# Fri3D_IRA_00.net
KiCad netlist of a schematic drawn in Altium Designer
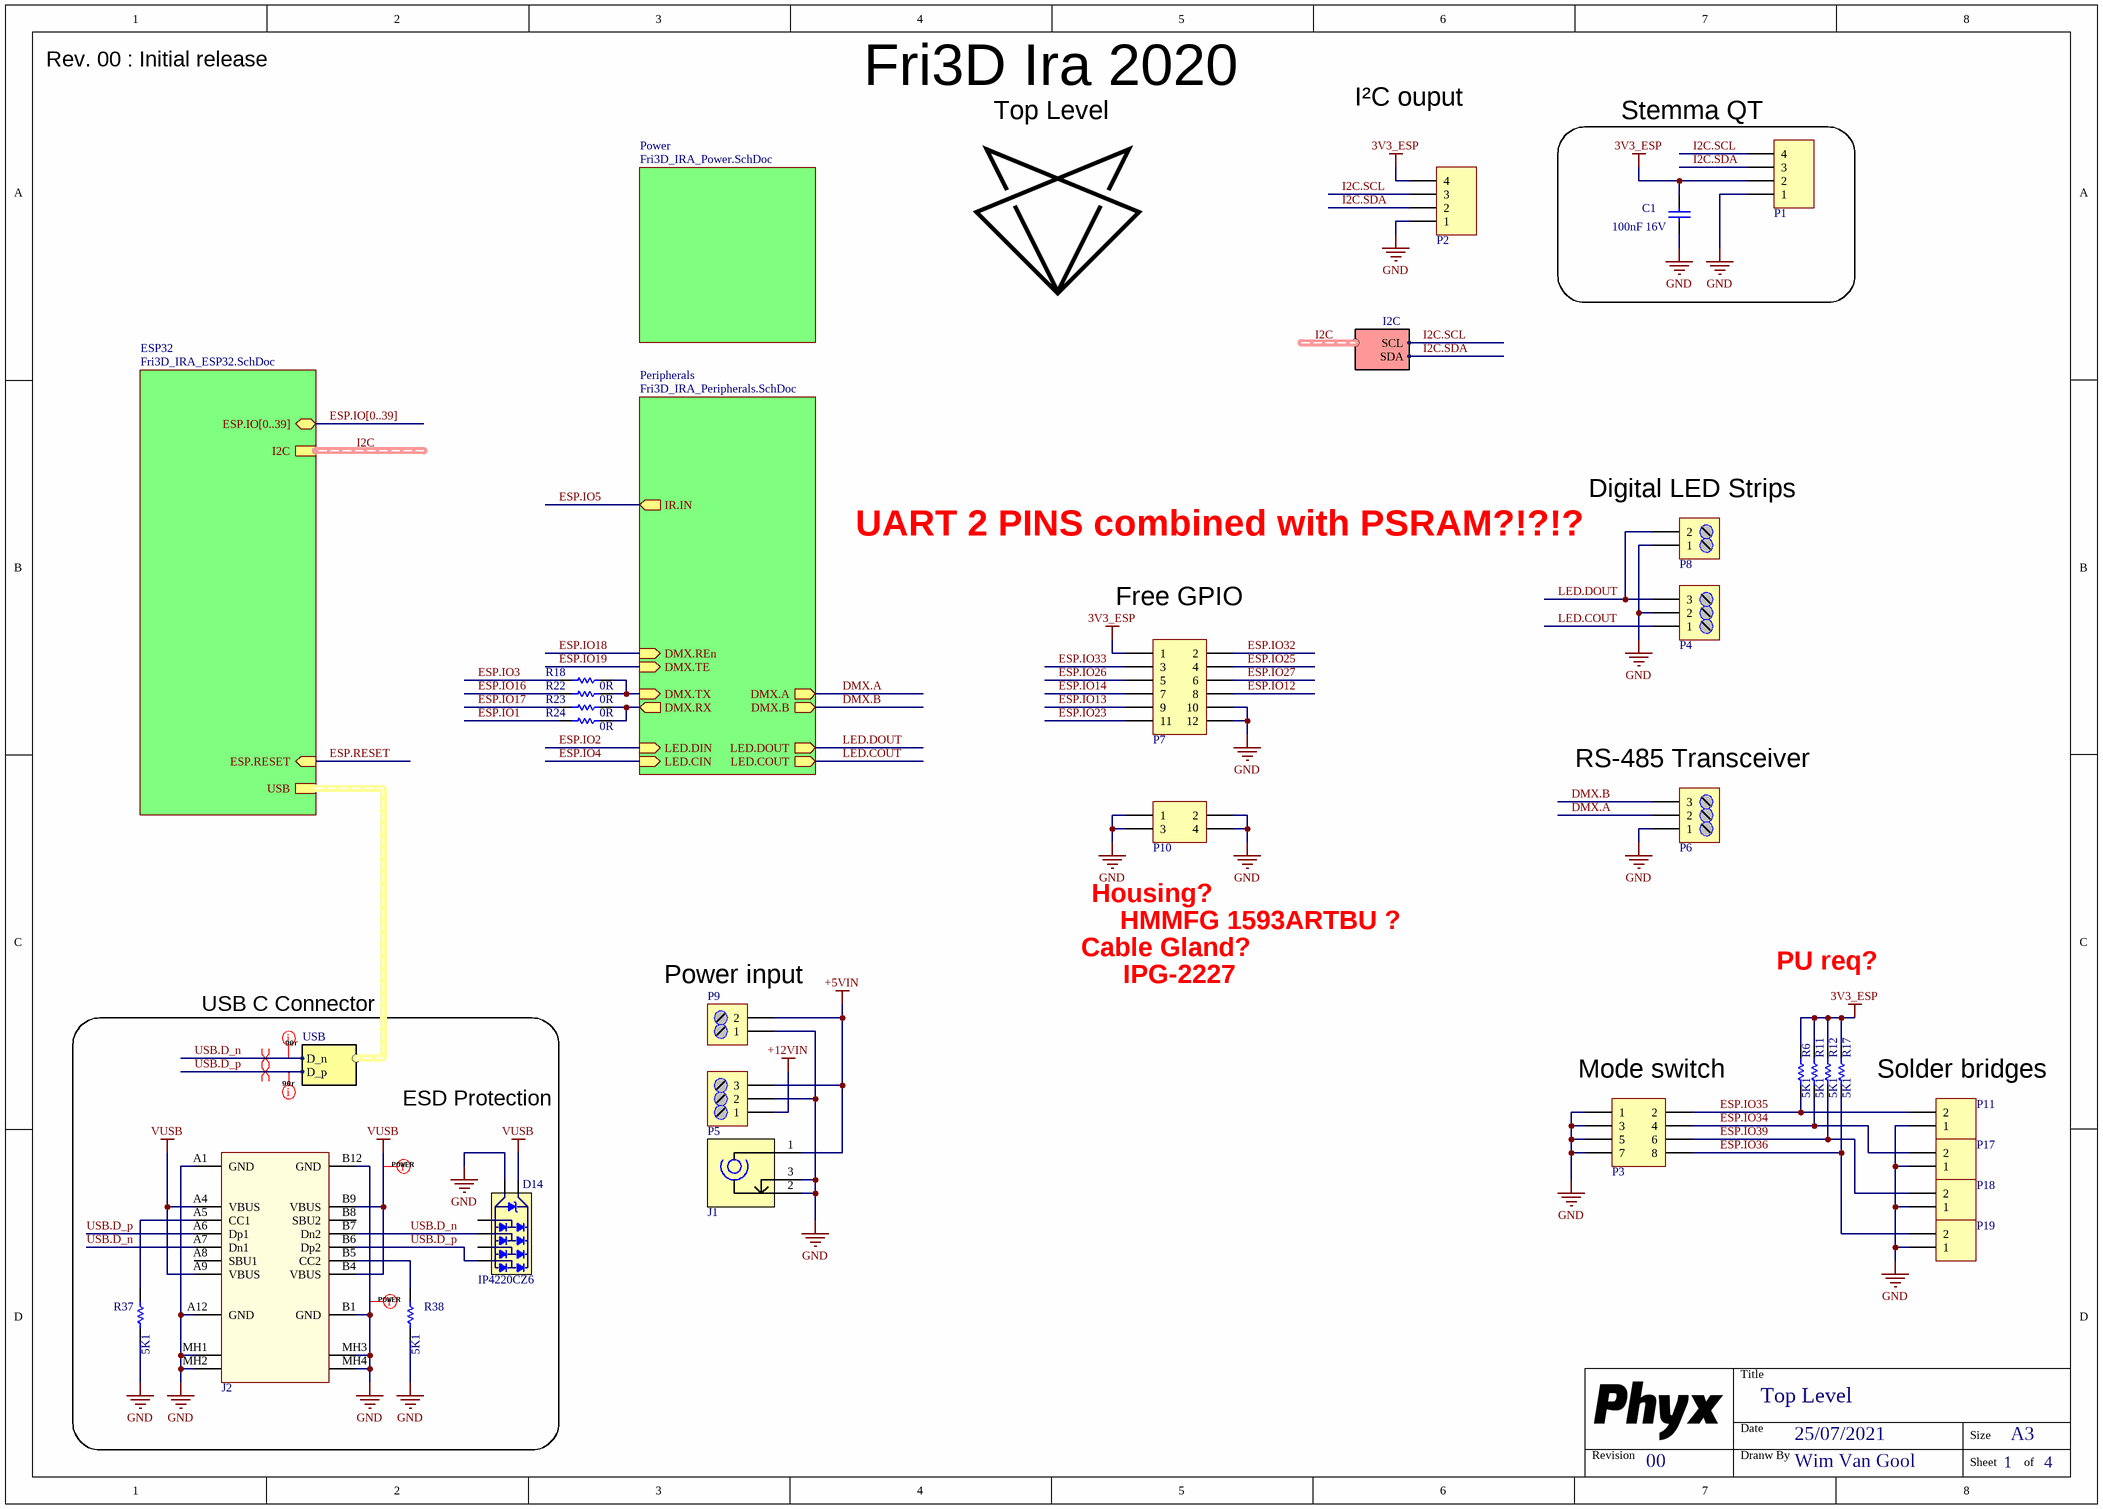
[diagram p0: Fri3D_IRA_00.SchDoc]

(export (version "E")
  (design (tool "Eeschema 10.0.6"))
  (components
    (comp (ref "C1")
      (value "100nF 16V")
      (footprint "C0603_N")
      (description "Capacitor Ceramic")
      (libsource (lib "Phyx_Components") (part "CAP_CERAMIC"))
    )
    (comp (ref "D14")
      (value "IP4220CZ6")
      (footprint "NXP_SOT457")
      (description "=Description")
      (fields (field (name "Comment") "TVS Diode Dual USB"))
      (libsource (lib "Phyx_Components") (part "NXP_IP4220CZ6"))
    )
    (comp (ref "J1")
      (value "Socket RA 5.5  with 2.5 barrel")
      (footprint "Cliff_DC10")
      (description "=Description")
      (libsource (lib "Phyx_Components") (part "Cliff_DC10"))
    )
    (comp (ref "J2")
      (value "USB 2.0 C Reversible Receptacle Horizontal")
      (footprint "HRO_TYPE-C-31-M-12")
      (libsource (lib "Phyx_Components") (part "USB_C_16_4"))
    )
    (comp (ref "P1")
      (value "Header 1.0mm RA Shrouded 4")
      (footprint "WE_665104131822")
      (libsource (lib "Phyx_Components") (part "Header 4"))
    )
    (comp (ref "P2")
      (value "Header 4")
      (footprint "HDR1X4")
      (libsource (lib "Phyx_Components") (part "Header 4"))
    )
    (comp (ref "P3")
      (value "Header 4x2")
      (footprint "HDR2X4")
      (libsource (lib "Phyx_Components") (part "Header 4X2"))
    )
    (comp (ref "P4")
      (value "3 Way Screw HDR 5,08mm")
      (footprint "TERM_BLK-0508-3-90")
      (libsource (lib "") (part "TERM_BLCK_3_1"))
    )
    (comp (ref "P5")
      (value "3 Way Screw HDR 5,08mm")
      (footprint "TERM_BLK-0508-3-90")
      (libsource (lib "Phyx_Components") (part "TERM_BLCK_3"))
    )
    (comp (ref "P6")
      (value "3 Way Screw HDR 5,08mm")
      (footprint "TERM_BLK-0508-3-90")
      (libsource (lib "") (part "TERM_BLCK_3_1"))
    )
    (comp (ref "P7")
      (value "Header 6X2")
      (footprint "HDR2X6")
      (libsource (lib "Phyx_Components") (part "Header 6X2"))
    )
    (comp (ref "P8")
      (value "2 Way Screw HDR 5,08mm")
      (footprint "TERM_BLK-0508-2-90")
      (libsource (lib "") (part "TERM_BLCK_2_1"))
    )
    (comp (ref "P9")
      (value "2 Way Screw HDR 5,08mm")
      (footprint "TERM_BLK-0508-2-90")
      (libsource (lib "Phyx_Components") (part "TERM_BLCK_2"))
    )
    (comp (ref "P10")
      (value "Header 2X2")
      (footprint "HDR2X2")
      (libsource (lib "Phyx_Components") (part "Header 2X2"))
    )
    (comp (ref "P11")
      (value "Easy to solder connection")
      (footprint "SOLDER_SW_V_1MM")
      (libsource (lib "Phyx_Components") (part "Header 2"))
    )
    (comp (ref "P17")
      (value "Easy to solder connection")
      (footprint "SOLDER_SW_V_1MM")
      (libsource (lib "Phyx_Components") (part "Header 2"))
    )
    (comp (ref "P18")
      (value "Easy to solder connection")
      (footprint "SOLDER_SW_V_1MM")
      (libsource (lib "Phyx_Components") (part "Header 2"))
    )
    (comp (ref "P19")
      (value "Easy to solder connection")
      (footprint "SOLDER_SW_V_1MM")
      (libsource (lib "Phyx_Components") (part "Header 2"))
    )
    (comp (ref "R6")
      (value "5K1")
      (footprint "R0603_N")
      (fields (field (name "Comment") "RESISTOR"))
      (libsource (lib "Phyx_Components") (part "RESISTOR"))
    )
    (comp (ref "R11")
      (value "5K1")
      (footprint "R0603_N")
      (fields (field (name "Comment") "RESISTOR"))
      (libsource (lib "Phyx_Components") (part "RESISTOR"))
    )
    (comp (ref "R12")
      (value "5K1")
      (footprint "R0603_N")
      (fields (field (name "Comment") "RESISTOR"))
      (libsource (lib "Phyx_Components") (part "RESISTOR"))
    )
    (comp (ref "R17")
      (value "5K1")
      (footprint "R0603_N")
      (fields (field (name "Comment") "RESISTOR"))
      (libsource (lib "Phyx_Components") (part "RESISTOR"))
    )
    (comp (ref "R18")
      (value "0R")
      (footprint "R0603_N")
      (description "RES # 0R 0603")
      (fields (field (name "Comment") "RESISTOR"))
      (libsource (lib "Phyx_Components") (part "RESISTOR"))
    )
    (comp (ref "R22")
      (value "0R")
      (footprint "R0603_N")
      (description "RES # 0R 0603")
      (fields (field (name "Comment") "RESISTOR"))
      (libsource (lib "Phyx_Components") (part "RESISTOR"))
    )
    (comp (ref "R23")
      (value "0R")
      (footprint "R0603_N")
      (description "RES # 0R 0603")
      (fields (field (name "Comment") "RESISTOR"))
      (libsource (lib "Phyx_Components") (part "RESISTOR"))
    )
    (comp (ref "R24")
      (value "0R")
      (footprint "R0603_N")
      (description "RES # 0R 0603")
      (fields (field (name "Comment") "RESISTOR"))
      (libsource (lib "Phyx_Components") (part "RESISTOR"))
    )
    (comp (ref "R37")
      (value "5K1")
      (footprint "R0603_N")
      (fields (field (name "Comment") "RESISTOR"))
      (libsource (lib "Phyx_Components") (part "RESISTOR"))
    )
    (comp (ref "R38")
      (value "5K1")
      (footprint "R0603_N")
      (fields (field (name "Comment") "RESISTOR"))
      (libsource (lib "Phyx_Components") (part "RESISTOR"))
    )
  )
  (nets
    (net (code "22") (name "+5VIN") (class "Default")
      (node (ref "J1") (pin "1") (pinfunction "1_1") (pintype "passive"))
      (node (ref "P5") (pin "3") (pinfunction "3_3") (pintype "passive"))
      (node (ref "P9") (pin "2") (pinfunction "2_2") (pintype "passive"))
    )
    (net (code "23") (name "+12VIN") (class "Default")
      (node (ref "P5") (pin "1") (pinfunction "1_1") (pintype "passive"))
    )
    (net (code "25") (name "/DMX.A") (class "Default")
      (node (ref "P6") (pin "2") (pinfunction "2_2") (pintype "passive"))
    )
    (net (code "26") (name "/DMX.B") (class "Default")
      (node (ref "P6") (pin "3") (pinfunction "3_3") (pintype "passive"))
    )
    (net (code "27") (name "/DMX.RX") (class "Default")
      (node (ref "R23") (pin "1") (pinfunction "1_1") (pintype "passive"))
      (node (ref "R24") (pin "1") (pinfunction "1_1") (pintype "passive"))
    )
    (net (code "28") (name "/DMX.TX") (class "Default")
      (node (ref "R18") (pin "1") (pinfunction "1_1") (pintype "passive"))
      (node (ref "R22") (pin "1") (pinfunction "1_1") (pintype "passive"))
    )
    (net (code "29") (name "/ESP.IO1") (class "Default")
      (node (ref "R24") (pin "2") (pinfunction "2_2") (pintype "passive"))
    )
    (net (code "31") (name "/ESP.IO3") (class "Default")
      (node (ref "R18") (pin "2") (pinfunction "2_2") (pintype "passive"))
    )
    (net (code "34") (name "/ESP.IO12") (class "Default")
      (node (ref "P7") (pin "8") (pinfunction "8_8") (pintype "passive"))
    )
    (net (code "35") (name "/ESP.IO13") (class "Default")
      (node (ref "P7") (pin "9") (pinfunction "9_9") (pintype "passive"))
    )
    (net (code "36") (name "/ESP.IO14") (class "Default")
      (node (ref "P7") (pin "7") (pinfunction "7_7") (pintype "passive"))
    )
    (net (code "37") (name "/ESP.IO16") (class "Default")
      (node (ref "R22") (pin "2") (pinfunction "2_2") (pintype "passive"))
    )
    (net (code "38") (name "/ESP.IO17") (class "Default")
      (node (ref "R23") (pin "2") (pinfunction "2_2") (pintype "passive"))
    )
    (net (code "41") (name "/ESP.IO23") (class "Default")
      (node (ref "P7") (pin "11") (pinfunction "11_11") (pintype "passive"))
    )
    (net (code "42") (name "/ESP.IO25") (class "Default")
      (node (ref "P7") (pin "4") (pinfunction "4_4") (pintype "passive"))
    )
    (net (code "43") (name "/ESP.IO26") (class "Default")
      (node (ref "P7") (pin "5") (pinfunction "5_5") (pintype "passive"))
    )
    (net (code "44") (name "/ESP.IO27") (class "Default")
      (node (ref "P7") (pin "6") (pinfunction "6_6") (pintype "passive"))
    )
    (net (code "45") (name "/ESP.IO32") (class "Default")
      (node (ref "P7") (pin "2") (pinfunction "2_2") (pintype "passive"))
    )
    (net (code "46") (name "/ESP.IO33") (class "Default")
      (node (ref "P7") (pin "3") (pinfunction "3_3") (pintype "passive"))
    )
    (net (code "47") (name "/ESP.IO34") (class "Default")
      (node (ref "P17") (pin "2") (pinfunction "2_2") (pintype "passive"))
      (node (ref "P3") (pin "4") (pinfunction "4_4") (pintype "passive"))
      (node (ref "R11") (pin "2") (pinfunction "2_2") (pintype "passive"))
    )
    (net (code "48") (name "/ESP.IO35") (class "Default")
      (node (ref "P11") (pin "2") (pinfunction "2_2") (pintype "passive"))
      (node (ref "P3") (pin "2") (pinfunction "2_2") (pintype "passive"))
      (node (ref "R6") (pin "2") (pinfunction "2_2") (pintype "passive"))
    )
    (net (code "49") (name "/ESP.IO36") (class "Default")
      (node (ref "P19") (pin "2") (pinfunction "2_2") (pintype "passive"))
      (node (ref "P3") (pin "8") (pinfunction "8_8") (pintype "passive"))
      (node (ref "R17") (pin "2") (pinfunction "2_2") (pintype "passive"))
    )
    (net (code "50") (name "/ESP.IO39") (class "Default")
      (node (ref "P18") (pin "2") (pinfunction "2_2") (pintype "passive"))
      (node (ref "P3") (pin "6") (pinfunction "6_6") (pintype "passive"))
      (node (ref "R12") (pin "2") (pinfunction "2_2") (pintype "passive"))
    )
    (net (code "53") (name "/I2C.SCL") (class "Default")
      (node (ref "P1") (pin "4") (pinfunction "4_4") (pintype "passive"))
      (node (ref "P2") (pin "3") (pinfunction "3_3") (pintype "passive"))
    )
    (net (code "54") (name "/I2C.SDA") (class "Default")
      (node (ref "P1") (pin "3") (pinfunction "3_3") (pintype "passive"))
      (node (ref "P2") (pin "2") (pinfunction "2_2") (pintype "passive"))
    )
    (net (code "56") (name "/LED.COUT") (class "Default")
      (node (ref "P4") (pin "1") (pinfunction "1_1") (pintype "passive"))
    )
    (net (code "57") (name "/LED.DOUT") (class "Default")
      (node (ref "P4") (pin "3") (pinfunction "3_3") (pintype "passive"))
      (node (ref "P8") (pin "2") (pinfunction "2_2") (pintype "passive"))
    )
    (net (code "58") (name "/USB.D_n") (class "Default")
      (node (ref "D14") (pin "1") (pinfunction "1_1") (pintype "passive"))
      (node (ref "J2") (pin "A7") (pinfunction "Dn1_A7") (pintype "passive"))
      (node (ref "J2") (pin "B7") (pinfunction "Dn2_B7") (pintype "passive"))
    )
    (net (code "59") (name "/USB.D_p") (class "Default")
      (node (ref "D14") (pin "6") (pinfunction "6_6") (pintype "passive"))
      (node (ref "J2") (pin "A6") (pinfunction "Dp1_A6") (pintype "passive"))
      (node (ref "J2") (pin "B6") (pinfunction "Dp2_B6") (pintype "passive"))
    )
    (net (code "62") (name "3V3_ESP") (class "Default")
      (node (ref "C1") (pin "1") (pinfunction "1_1") (pintype "passive"))
      (node (ref "P1") (pin "2") (pinfunction "2_2") (pintype "passive"))
      (node (ref "P2") (pin "4") (pinfunction "4_4") (pintype "passive"))
      (node (ref "P7") (pin "1") (pinfunction "1_1") (pintype "passive"))
      (node (ref "R11") (pin "1") (pinfunction "1_1") (pintype "passive"))
      (node (ref "R12") (pin "1") (pinfunction "1_1") (pintype "passive"))
      (node (ref "R17") (pin "1") (pinfunction "1_1") (pintype "passive"))
      (node (ref "R6") (pin "1") (pinfunction "1_1") (pintype "passive"))
    )
    (net (code "63") (name "GND") (class "Default")
      (node (ref "C1") (pin "2") (pinfunction "2_2") (pintype "passive"))
      (node (ref "D14") (pin "2") (pinfunction "GND_2") (pintype "passive"))
      (node (ref "J1") (pin "2") (pinfunction "2_2") (pintype "passive"))
      (node (ref "J1") (pin "3") (pinfunction "3_3") (pintype "passive"))
      (node (ref "J2") (pin "A1") (pinfunction "GND_A1") (pintype "passive"))
      (node (ref "J2") (pin "A12") (pinfunction "GND_A12") (pintype "passive"))
      (node (ref "J2") (pin "B1") (pinfunction "GND_B1") (pintype "passive"))
      (node (ref "J2") (pin "B12") (pinfunction "GND_B12") (pintype "passive"))
      (node (ref "J2") (pin "MH1") (pinfunction "Tab_MH1") (pintype "passive"))
      (node (ref "J2") (pin "MH2") (pinfunction "Tab_MH2") (pintype "passive"))
      (node (ref "J2") (pin "MH3") (pinfunction "Tab_MH3") (pintype "passive"))
      (node (ref "J2") (pin "MH4") (pinfunction "Tab_MH4") (pintype "passive"))
      (node (ref "P1") (pin "1") (pinfunction "1_1") (pintype "passive"))
      (node (ref "P10") (pin "1") (pinfunction "1_1") (pintype "passive"))
      (node (ref "P10") (pin "2") (pinfunction "2_2") (pintype "passive"))
      (node (ref "P10") (pin "3") (pinfunction "3_3") (pintype "passive"))
      (node (ref "P10") (pin "4") (pinfunction "4_4") (pintype "passive"))
      (node (ref "P11") (pin "1") (pinfunction "1_1") (pintype "passive"))
      (node (ref "P17") (pin "1") (pinfunction "1_1") (pintype "passive"))
      (node (ref "P18") (pin "1") (pinfunction "1_1") (pintype "passive"))
      (node (ref "P19") (pin "1") (pinfunction "1_1") (pintype "passive"))
      (node (ref "P2") (pin "1") (pinfunction "1_1") (pintype "passive"))
      (node (ref "P3") (pin "1") (pinfunction "1_1") (pintype "passive"))
      (node (ref "P3") (pin "3") (pinfunction "3_3") (pintype "passive"))
      (node (ref "P3") (pin "5") (pinfunction "5_5") (pintype "passive"))
      (node (ref "P3") (pin "7") (pinfunction "7_7") (pintype "passive"))
      (node (ref "P4") (pin "2") (pinfunction "2_2") (pintype "passive"))
      (node (ref "P5") (pin "2") (pinfunction "2_2") (pintype "passive"))
      (node (ref "P6") (pin "1") (pinfunction "1_1") (pintype "passive"))
      (node (ref "P7") (pin "10") (pinfunction "10_10") (pintype "passive"))
      (node (ref "P7") (pin "12") (pinfunction "12_12") (pintype "passive"))
      (node (ref "P8") (pin "1") (pinfunction "1_1") (pintype "passive"))
      (node (ref "P9") (pin "1") (pinfunction "1_1") (pintype "passive"))
      (node (ref "R37") (pin "2") (pinfunction "2_2") (pintype "passive"))
      (node (ref "R38") (pin "2") (pinfunction "2_2") (pintype "passive"))
    )
    (net (code "64") (name "Net-(J2-CC1)") (class "Default")
      (node (ref "J2") (pin "A5") (pinfunction "CC1_A5") (pintype "passive"))
      (node (ref "R37") (pin "1") (pinfunction "1_1") (pintype "passive"))
    )
    (net (code "65") (name "Net-(J2-CC2)") (class "Default")
      (node (ref "J2") (pin "B5") (pinfunction "CC2_B5") (pintype "passive"))
      (node (ref "R38") (pin "1") (pinfunction "1_1") (pintype "passive"))
    )
    (net (code "66") (name "VUSB") (class "Default")
      (node (ref "D14") (pin "5") (pinfunction "VBus_5") (pintype "passive"))
      (node (ref "J2") (pin "A4") (pinfunction "VBUS_A4") (pintype "passive"))
      (node (ref "J2") (pin "A9") (pinfunction "VBUS_A9") (pintype "passive"))
      (node (ref "J2") (pin "B4") (pinfunction "VBUS_B4") (pintype "passive"))
      (node (ref "J2") (pin "B9") (pinfunction "VBUS_B9") (pintype "passive"))
    )
    (net (code "67") (name "unconnected-(D14-Pad3)") (class "Default")
      (node (ref "D14") (pin "3") (pinfunction "3_3") (pintype "passive"))
    )
    (net (code "68") (name "unconnected-(D14-Pad4)") (class "Default")
      (node (ref "D14") (pin "4") (pinfunction "4_4") (pintype "passive"))
    )
    (net (code "69") (name "unconnected-(J2-SBU1-PadA8)") (class "Default")
      (node (ref "J2") (pin "A8") (pinfunction "SBU1_A8") (pintype "passive"))
    )
    (net (code "70") (name "unconnected-(J2-SBU2-PadB8)") (class "Default")
      (node (ref "J2") (pin "B8") (pinfunction "SBU2_B8") (pintype "passive"))
    )
  )
)
